# SolarSenseMaster.net
KiCad netlist of a schematic drawn in Altium Designer
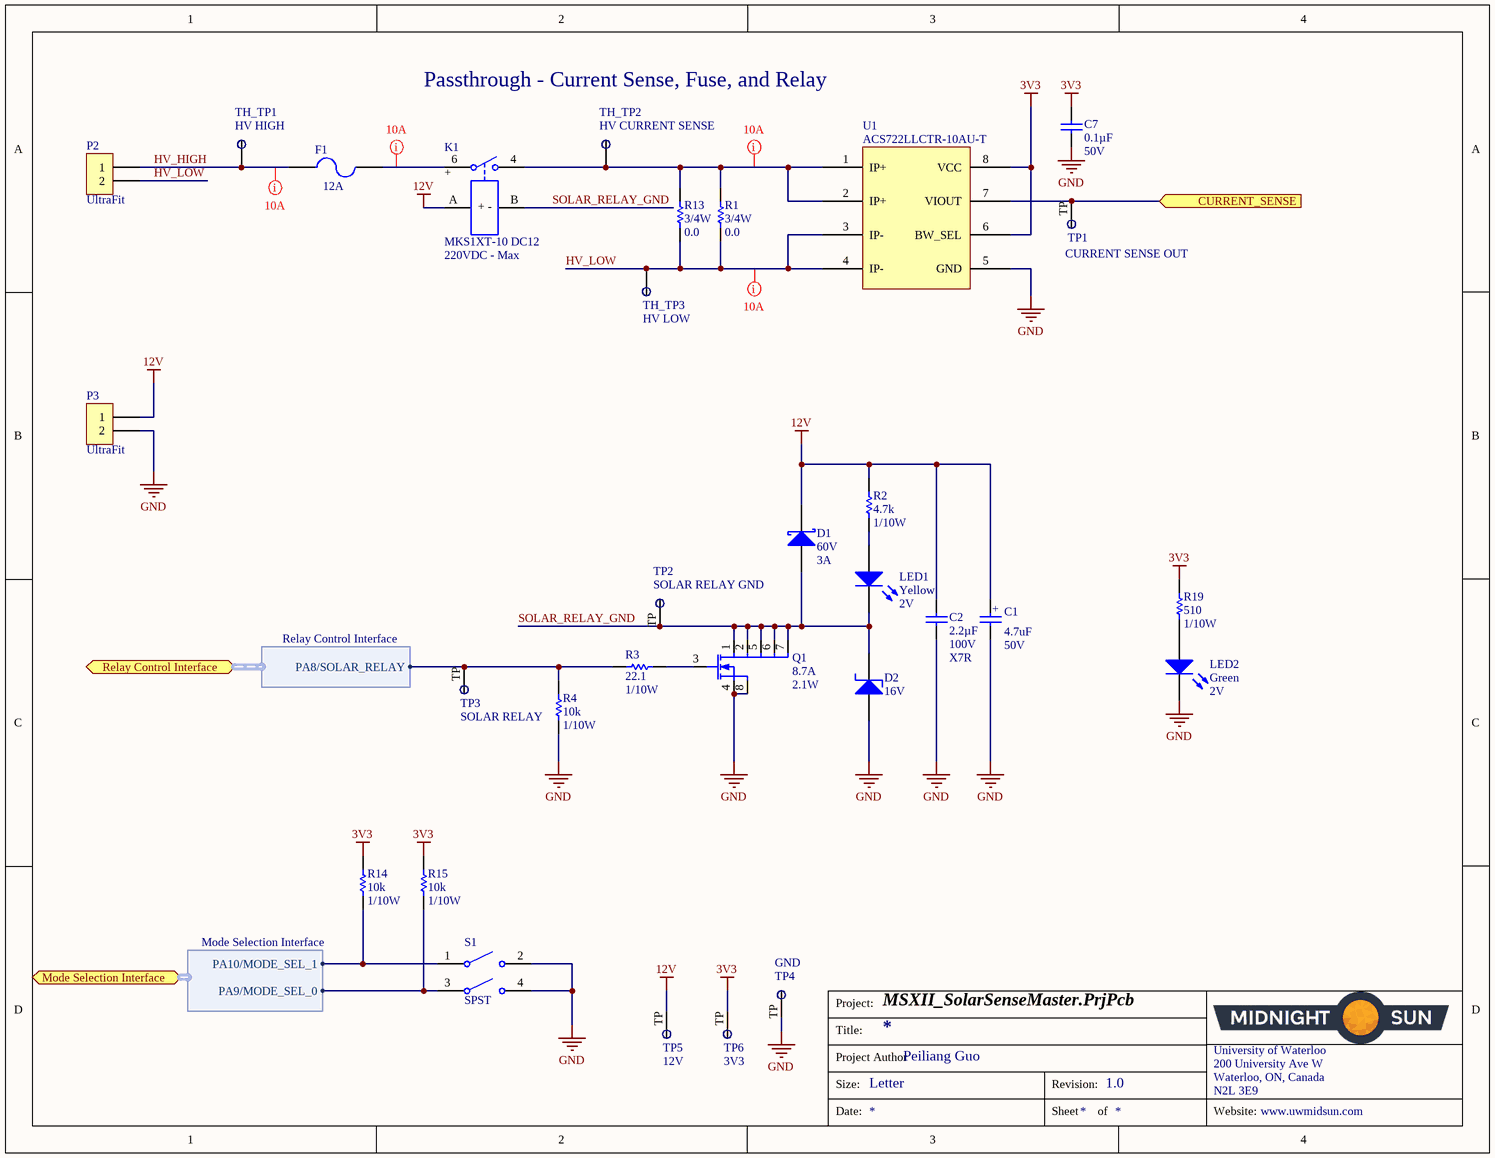
[diagram p0: SolarSenseMaster.SchDoc]

(export (version "E")
  (design (tool "Eeschema 10.0.6"))
  (components
    (comp (ref "C1")
      (value "EEE-1HA4R7NP")
      (footprint "CAP ALUM 6.3MM RADIAL SMD")
      (description "4.7µF 50V Aluminum Electrolytic Capacitors Radial, Can - SMD 2000 Hrs @ 85°C")
      (fields
        (field (name "TOLERANCE") "20%")
        (field (name "CAPACITANCE") "4.7uF")
        (field (name "VOLTAGE RATING (DC)") "50V")
      )
      (libsource (lib "Schematic Diagrams") (part "CAP ALUM 4.7UF 20% 50V SMD"))
    )
    (comp (ref "C2")
      (value "CAP CER 2.2UF 100V ±20% X7R 1206")
      (footprint "CAP, 1206")
      (description "2.2µF ±20% 100V Ceramic Capacitor X7R 1206 (3216 Metric)")
      (fields
        (field (name "TOLERANCE") "±20%")
        (field (name "CAPACITANCE") "2.2µF")
        (field (name "VOLTAGE") "100V")
        (field (name "TEMPERATURE COEFFICIENT") "X7R")
      )
      (libsource (lib "Schematic Diagrams") (part "CAP CER 2.2UF 100V ±20% X7R 1206"))
    )
    (comp (ref "C7")
      (value "CAP CER 0.1UF 50V 10% X7R 0603")
      (footprint "CAP, 0603")
      (description "0.10µF ±10% 50V Ceramic Capacitor X7R 0603 (1608 Metric)")
      (fields
        (field (name "TOLERANCE") "±10%")
        (field (name "CAPACITANCE") "0.1µF")
        (field (name "VOLTAGE") "50V")
      )
      (libsource (lib "Schematic Diagrams") (part "CAP CER 0.1UF 50V 10% X7R 0603"))
    )
    (comp (ref "D1")
      (value "DIODE SCHOTTKY 60V 3A SMA")
      (footprint "Diode, SMA")
      (description "Diode Schottky 60V 3A Surface Mount SMA")
      (fields
        (field (name "VOLTAGE - DC REVERSE (VR) (MAX)") "60V")
        (field (name "CURRENT - AVERAGE RECTIFIED (IO)") "3A")
      )
      (libsource (lib "Schematic Diagrams") (part "DIODE SCHOTTKY 60V 3A SMA"))
    )
    (comp (ref "D2")
      (value "DIODE ZENER 16V 5W DO-214AA (SMB)")
      (footprint "DO-214AA Diode")
      (description "Zener Diode 16V 5W ±5% Surface Mount DO-214AA (SMB)")
      (fields
        (field (name "MANUFACTURE PART NUMBER") "SMBJ5353B-TP")
        (field (name "VOLTAGE - ZENER (NOM)") "16V")
      )
      (libsource (lib "Schematic Diagrams") (part "DIODE ZENER 16V 5W DO-214AA (SMB)"))
    )
    (comp (ref "F1")
      (value "FUSE 12 A 600VAC/DC KLM-12")
      (footprint "FUSE CLIPS 1A3400-09-R")
      (description "FUSE CRTRDGE 12A 600VAC/VDC 5AG")
      (fields
        (field (name "MANUFACTURER") "Eaton")
        (field (name "MANUFACTURER PART NUMBER") "KLM-12")
        (field (name "CURRENT RATING") "12A")
      )
      (libsource (lib "Schematic Diagrams") (part "FUSE 12 A 600VAC/DC KLM-12"))
    )
    (comp (ref "K1")
      (value "RELAY SPST 12V 10A")
      (footprint "RELAY SOCKET P7M-06P")
      (description "General Purpose Relay SPST-NO (1 Form A) 12VDC Coil Socketable")
      (fields
        (field (name "MANUFACTURER") "Omron Automation and Safety")
        (field (name "MANUFACTURER PART NUMBER") "MKS1XT-10 DC12")
        (field (name "SWITCHING VOLTAGE") "220VDC - Max")
      )
      (libsource (lib "Schematic Diagrams") (part "RELAY SPST 12V 10A"))
    )
    (comp (ref "LED1")
      (value "LED YELLOW CLEAR 2.1V 0603")
      (footprint "LED_0603")
      (description "Yellow 590nm LED Indication - Discrete 2V 0603 (1608 Metric)")
      (fields
        (field (name "MANUFACTURER") "Wurth Electronics Inc.")
        (field (name "MANUFACTURER PART NUMBER") "150060YS75000")
        (field (name "COLOR") "Yellow")
        (field (name "VOLTAGE - FORWARD (VF) (TYP)") "2V")
      )
      (libsource (lib "Schematic Diagrams") (part "LED YELLOW CLEAR 2.1V 0603"))
    )
    (comp (ref "LED2")
      (value "LED GREEN CLEAR 2V 0603")
      (footprint "LED_0603")
      (description "Green 572nm LED Indication - Discrete 2V 0603 (1608 Metric)")
      (fields
        (field (name "MANUFACTURER") "Wurth Electronics Inc.")
        (field (name "MANUFACTURER PART NUMBER") "150060VS75000")
        (field (name "COLOR") "Green")
        (field (name "VOLTAGE - FORWARD (VF) (TYP)") "2V")
      )
      (libsource (lib "Schematic Diagrams") (part "LED GREEN CLEAR 2V 0603"))
    )
    (comp (ref "P2")
      (value "CONN 2POS ULTRA-FIT 0.138\"")
      (footprint "CONN, 2POS ULTRA-FIT")
      (description "2 Positions Header, Shrouded Connector 0.138\" (3.50mm) Through Hole Gold")
      (fields (field (name "VOLTAGE") "400V") (field (name "SERIES") "UltraFit"))
      (libsource (lib "Schematic Diagrams") (part "CONN 2POS ULTRA-FIT 0.138{dblquote}"))
    )
    (comp (ref "P3")
      (value "CONN 2POS ULTRA-FIT 0.138\"")
      (footprint "CONN, 2POS ULTRA-FIT")
      (description "2 Positions Header, Shrouded Connector 0.138\" (3.50mm) Through Hole Gold")
      (fields (field (name "VOLTAGE") "400V") (field (name "SERIES") "UltraFit"))
      (libsource (lib "Schematic Diagrams") (part "CONN 2POS ULTRA-FIT 0.138{dblquote}"))
    )
    (comp (ref "Q1")
      (value "MOSFET N-CH 30V 8.7A 2.1W 6-PQFN (2x2)")
      (footprint "MOSFET N-CH 30V 12A 2mmx2mm PQFN")
      (fields
        (field (name "CURRENT - CONTINUOUS DRAIN (ID) @ 25°C") "8.7A")
        (field (name "POWER DISSIPATION (MAX)") "2.1W")
      )
      (libsource (lib "Schematic Diagrams") (part "MOSFET N-CH 30V 8.7A 2.1W 6-PQFN (2x2)"))
    )
    (comp (ref "R1")
      (value "RES 0.0 OHM 3/4W 1206")
      (footprint "RES 1206")
      (description "0 Ohms Jumper 0.75W, 3/4W Chip Resistor 1206 (3216 Metric) Automotive AEC-Q200 Metal Foil")
      (fields
        (field (name "MANUFACTURER") "Stackpole Electronics Inc.")
        (field (name "MANUFACTURER PART NUMBER") "HCJ1206ZT0R00")
        (field (name "POWER (WATTS)") "3/4W")
        (field (name "RESISTANCE") "0.0")
      )
      (libsource (lib "Schematic Diagrams") (part "RES 0.0 OHM 3/4W 1206"))
    )
    (comp (ref "R2")
      (value "RES 4.7K OHM 1% 1/10W 0603")
      (footprint "RES, 0603")
      (description "4.7k Ohm ±1% 0.1W, 1/10W Chip Resistor 0603 (1608 Metric) Moisture Resistant Thick Film")
      (fields
        (field (name "TOLERANCE") "±1%")
        (field (name "RESISTANCE (OHMS)") "4.7k")
        (field (name "POWER (WATTS)") "1/10W")
      )
      (libsource (lib "Schematic Diagrams") (part "RES 4.7K OHM 1% 1/10W 0603"))
    )
    (comp (ref "R3")
      (value "RES 22.1 OHM 1% 1/10W 0603")
      (footprint "RES, 0603")
      (description "22.1 Ohm ±1% 0.1W, 1/10W Chip Resistor 0603 (1608 Metric) Moisture Resistant Thick Film")
      (fields
        (field (name "TOLERANCE") "±1%")
        (field (name "RESISTANCE") "22.1")
        (field (name "POWER") "1/10W")
      )
      (libsource (lib "Schematic Diagrams") (part "RES 22.1 OHM 1% 1/10W 0603"))
    )
    (comp (ref "R4")
      (value "RES 10K OHM 1% 1/10W 0603")
      (footprint "RES, 0603")
      (description "RES SMD 10K OHM 1% 1/10W 0603")
      (fields
        (field (name "TOLERANCE") "±1%")
        (field (name "RESISTANCE") "10k")
        (field (name "POWER") "1/10W")
      )
      (libsource (lib "Schematic Diagrams") (part "RES 10K OHM 1% 1/10W 0603"))
    )
    (comp (ref "R13")
      (value "RES 0.0 OHM 3/4W 1206")
      (footprint "RES 1206")
      (description "0 Ohms Jumper 0.75W, 3/4W Chip Resistor 1206 (3216 Metric) Automotive AEC-Q200 Metal Foil")
      (fields
        (field (name "MANUFACTURER") "Stackpole Electronics Inc.")
        (field (name "MANUFACTURER PART NUMBER") "HCJ1206ZT0R00")
        (field (name "POWER (WATTS)") "3/4W")
        (field (name "RESISTANCE") "0.0")
      )
      (libsource (lib "Schematic Diagrams") (part "RES 0.0 OHM 3/4W 1206"))
    )
    (comp (ref "R14")
      (value "RES 10K OHM 1% 1/10W 0603")
      (footprint "RES, 0603")
      (description "RES SMD 10K OHM 1% 1/10W 0603")
      (fields
        (field (name "TOLERANCE") "±1%")
        (field (name "RESISTANCE") "10k")
        (field (name "POWER") "1/10W")
      )
      (libsource (lib "Schematic Diagrams") (part "RES 10K OHM 1% 1/10W 0603"))
    )
    (comp (ref "R15")
      (value "RES 10K OHM 1% 1/10W 0603")
      (footprint "RES, 0603")
      (description "RES SMD 10K OHM 1% 1/10W 0603")
      (fields
        (field (name "TOLERANCE") "±1%")
        (field (name "RESISTANCE") "10k")
        (field (name "POWER") "1/10W")
      )
      (libsource (lib "Schematic Diagrams") (part "RES 10K OHM 1% 1/10W 0603"))
    )
    (comp (ref "R19")
      (value "RES 510 OHM 5% 1/10W 0603")
      (footprint "RES, 0603")
      (description "RES SMD 510 OHM 5% 1/10W 0603")
      (fields
        (field (name "TOLERANCE") "±5%")
        (field (name "RESISTANCE") "510")
        (field (name "POWER") "1/10W")
      )
      (libsource (lib "Schematic Diagrams") (part "RES 510 OHM 5% 1/10W 0603"))
    )
    (comp (ref "S1")
      (value "SPST")
      (footprint "SW SPST 2POS DIP 0.1A 20V")
      (description "SWITCH SLIDE DIP SPST 100MA 20V")
      (fields
        (field (name "MANUFACTURER") "CTS Electrocomponents")
        (field (name "MANUFACTURER PART NUMBER") "219-2MST")
      )
      (libsource (lib "Schematic Diagrams") (part "SW SPST 2POS DIP 0.1A 20V"))
    )
    (comp (ref "TH_TP1")
      (value "HV HIGH")
      (footprint "Thru Test Point")
      (libsource (lib "Schematic Diagrams") (part "Thru Test Point"))
    )
    (comp (ref "TH_TP2")
      (value "HV CURRENT SENSE")
      (footprint "Thru Test Point")
      (libsource (lib "Schematic Diagrams") (part "Thru Test Point"))
    )
    (comp (ref "TH_TP3")
      (value "HV LOW")
      (footprint "Thru Test Point")
      (libsource (lib "Schematic Diagrams") (part "Thru Test Point"))
    )
    (comp (ref "TP1")
      (value "CURRENT SENSE OUT")
      (footprint "Test Point")
      (libsource (lib "Schematic Diagrams") (part "Test Point"))
    )
    (comp (ref "TP2")
      (value "SOLAR RELAY GND")
      (footprint "Test Point")
      (libsource (lib "Schematic Diagrams") (part "Test Point"))
    )
    (comp (ref "TP3")
      (value "SOLAR RELAY")
      (footprint "Test Point")
      (libsource (lib "Schematic Diagrams") (part "Test Point"))
    )
    (comp (ref "TP4")
      (value "GND")
      (footprint "Test Point")
      (libsource (lib "Schematic Diagrams") (part "Test Point"))
    )
    (comp (ref "TP5")
      (value "12V")
      (footprint "Test Point")
      (libsource (lib "Schematic Diagrams") (part "Test Point"))
    )
    (comp (ref "TP6")
      (value "3V3")
      (footprint "Test Point")
      (libsource (lib "Schematic Diagrams") (part "Test Point"))
    )
    (comp (ref "U1")
      (value "IC CURRENT SENSOR HALL EFFECT 8-SOIC")
      (footprint "SOIC8")
      (description "Current Sensor 10A 1 Channel Hall Effect, Open Loop Unidirectional 8-SOIC (0.154\", 3.90mm Width)")
      (fields
        (field (name "MANUFACTURER") "Allegro MicroSystems, LLC")
        (field (name "MANUFACTURER PART NUMBER") "ACS722LLCTR-10AU-T")
      )
      (libsource (lib "Schematic Diagrams") (part "IC CURRENT SENSOR HALL EFFECT 8-SOIC"))
    )
  )
  (nets
    (net (code "6") (name "/CURRENT_SENSE") (class "Default")
      (node (ref "TP1") (pin "TP") (pinfunction "1_TP") (pintype "passive"))
      (node (ref "U1") (pin "7") (pinfunction "VIOUT_7") (pintype "passive"))
    )
    (net (code "7") (name "/HV_HIGH") (class "Default")
      (node (ref "F1") (pin "1") (pinfunction "1_1") (pintype "passive"))
      (node (ref "P2") (pin "1") (pinfunction "1_1") (pintype "passive"))
      (node (ref "TH_TP1") (pin "TH_TP") (pinfunction "1_TH_TP") (pintype "passive"))
    )
    (net (code "8") (name "/HV_LOW") (class "Default")
      (node (ref "P2") (pin "2") (pinfunction "2_2") (pintype "passive"))
      (node (ref "R1") (pin "2") (pinfunction "2_2") (pintype "passive"))
      (node (ref "R13") (pin "2") (pinfunction "2_2") (pintype "passive"))
      (node (ref "TH_TP3") (pin "TH_TP") (pinfunction "1_TH_TP") (pintype "passive"))
      (node (ref "U1") (pin "3") (pinfunction "IP-_3") (pintype "passive"))
      (node (ref "U1") (pin "4") (pinfunction "IP-_4") (pintype "passive"))
    )
    (net (code "9") (name "/SOLAR_RELAY_GND") (class "Default")
      (node (ref "D1") (pin "1") (pinfunction "1_1") (pintype "passive"))
      (node (ref "D2") (pin "2") (pinfunction "K_2") (pintype "passive"))
      (node (ref "K1") (pin "B") (pinfunction "-_B") (pintype "passive"))
      (node (ref "LED1") (pin "2") (pinfunction "K_2") (pintype "passive"))
      (node (ref "Q1") (pin "1") (pinfunction "D_1") (pintype "passive"))
      (node (ref "Q1") (pin "2") (pinfunction "D_2") (pintype "passive"))
      (node (ref "Q1") (pin "5") (pinfunction "D_5") (pintype "passive"))
      (node (ref "Q1") (pin "6") (pinfunction "D_6") (pintype "passive"))
      (node (ref "Q1") (pin "7") (pinfunction "D_7") (pintype "passive"))
      (node (ref "TP2") (pin "TP") (pinfunction "1_TP") (pintype "passive"))
    )
    (net (code "12") (name "3V3") (class "Default")
      (node (ref "C7") (pin "1") (pinfunction "1_1") (pintype "passive"))
      (node (ref "R14") (pin "1") (pinfunction "1_1") (pintype "passive"))
      (node (ref "R15") (pin "1") (pinfunction "1_1") (pintype "passive"))
      (node (ref "R19") (pin "1") (pinfunction "1_1") (pintype "passive"))
      (node (ref "TP6") (pin "TP") (pinfunction "1_TP") (pintype "passive"))
      (node (ref "U1") (pin "6") (pinfunction "BW_SEL_6") (pintype "passive"))
      (node (ref "U1") (pin "8") (pinfunction "VCC_8") (pintype "passive"))
    )
    (net (code "13") (name "12V") (class "Default")
      (node (ref "C1") (pin "1") (pinfunction "1_1") (pintype "passive"))
      (node (ref "C2") (pin "1") (pinfunction "1_1") (pintype "passive"))
      (node (ref "D1") (pin "2") (pinfunction "2_2") (pintype "passive"))
      (node (ref "K1") (pin "A") (pinfunction "+_A") (pintype "passive"))
      (node (ref "P3") (pin "1") (pinfunction "1_1") (pintype "passive"))
      (node (ref "R2") (pin "1") (pinfunction "1_1") (pintype "passive"))
      (node (ref "TP5") (pin "TP") (pinfunction "1_TP") (pintype "passive"))
    )
    (net (code "14") (name "GND") (class "Default")
      (node (ref "C1") (pin "2") (pinfunction "2_2") (pintype "passive"))
      (node (ref "C2") (pin "2") (pinfunction "2_2") (pintype "passive"))
      (node (ref "C7") (pin "2") (pinfunction "2_2") (pintype "passive"))
      (node (ref "D2") (pin "1") (pinfunction "A_1") (pintype "passive"))
      (node (ref "LED2") (pin "2") (pinfunction "K_2") (pintype "passive"))
      (node (ref "P3") (pin "2") (pinfunction "2_2") (pintype "passive"))
      (node (ref "Q1") (pin "4") (pinfunction "S_4") (pintype "passive"))
      (node (ref "Q1") (pin "8") (pinfunction "S_8") (pintype "passive"))
      (node (ref "R4") (pin "2") (pinfunction "2_2") (pintype "passive"))
      (node (ref "S1") (pin "2") (pinfunction "2_2") (pintype "passive"))
      (node (ref "S1") (pin "4") (pinfunction "4_4") (pintype "passive"))
      (node (ref "TP4") (pin "TP") (pinfunction "1_TP") (pintype "passive"))
      (node (ref "U1") (pin "5") (pinfunction "GND_5") (pintype "passive"))
    )
    (net (code "15") (name "Net-(F1-Pad2)") (class "Default")
      (node (ref "F1") (pin "2") (pinfunction "2_2") (pintype "passive"))
      (node (ref "K1") (pin "6") (pintype "passive"))
    )
    (net (code "16") (name "Net-(LED1-A)") (class "Default")
      (node (ref "LED1") (pin "1") (pinfunction "A_1") (pintype "passive"))
      (node (ref "R2") (pin "2") (pinfunction "2_2") (pintype "passive"))
    )
    (net (code "17") (name "Net-(LED2-A)") (class "Default")
      (node (ref "LED2") (pin "1") (pinfunction "A_1") (pintype "passive"))
      (node (ref "R19") (pin "2") (pinfunction "2_2") (pintype "passive"))
    )
    (net (code "18") (name "Net-(Q1-G)") (class "Default")
      (node (ref "Q1") (pin "3") (pinfunction "G_3") (pintype "passive"))
      (node (ref "R3") (pin "2") (pinfunction "2_2") (pintype "passive"))
    )
    (net (code "19") (name "Net-(R14-Pad2)") (class "Default")
      (node (ref "R14") (pin "2") (pinfunction "2_2") (pintype "passive"))
      (node (ref "S1") (pin "1") (pinfunction "1_1") (pintype "passive"))
    )
    (net (code "20") (name "Net-(R15-Pad2)") (class "Default")
      (node (ref "R15") (pin "2") (pinfunction "2_2") (pintype "passive"))
      (node (ref "S1") (pin "3") (pinfunction "3_3") (pintype "passive"))
    )
    (net (code "21") (name "Net-(TH_TP2-1)") (class "Default")
      (node (ref "K1") (pin "4") (pinfunction "4_4") (pintype "passive"))
      (node (ref "R1") (pin "1") (pinfunction "1_1") (pintype "passive"))
      (node (ref "R13") (pin "1") (pinfunction "1_1") (pintype "passive"))
      (node (ref "TH_TP2") (pin "TH_TP") (pinfunction "1_TH_TP") (pintype "passive"))
      (node (ref "U1") (pin "1") (pinfunction "IP+_1") (pintype "passive"))
      (node (ref "U1") (pin "2") (pinfunction "IP+_2") (pintype "passive"))
    )
    (net (code "22") (name "Net-(TP3-1)") (class "Default")
      (node (ref "R3") (pin "1") (pinfunction "1_1") (pintype "passive"))
      (node (ref "R4") (pin "1") (pinfunction "1_1") (pintype "passive"))
      (node (ref "TP3") (pin "TP") (pinfunction "1_TP") (pintype "passive"))
    )
  )
)
